# Sheet1.net
KiCad netlist of a schematic drawn in Altium Designer
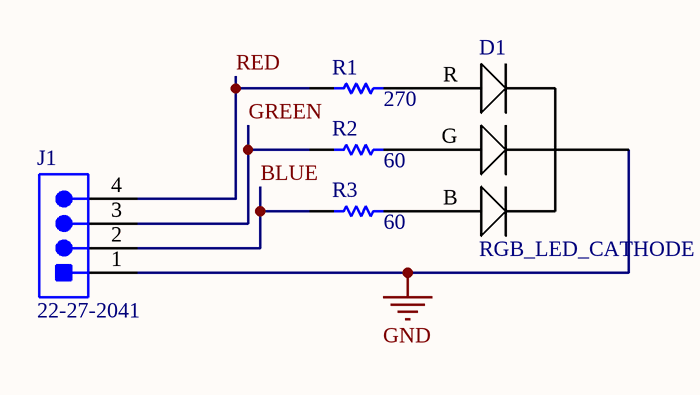
[diagram p0: Sheet1.SchDoc]

(export (version "E")
  (design (tool "Eeschema 10.0.6"))
  (components
    (comp (ref "D1")
      (value "RGB_LED_CATHODE")
      (footprint "RGB_LED_Cathode")
      (libsource (lib "RowanIntegratedLibrary1") (part "RGB_LED_CATHODE"))
    )
    (comp (ref "J1")
      (value "22-27-2041")
      (footprint "MOLX-22-27-2041_V")
      (description "Male Header, Pitch 2.54 mm, 1 x 4 Position, Height 11.7 mm, Tail Length 3.56 mm, RoHS, Bulk")
      (fields (field (name "MANUFACTURER") "Molex"))
      (libsource (lib "Altium Content Vault") (part "CN-1P-M-R4"))
    )
    (comp (ref "R1")
      (value "270")
      (footprint "RESC0805(2012)_L")
      (description "243K 0.125W 1% 0805 (2012 Metric)  SMD")
      (fields (field (name "POWER") "0.125 W") (field (name "TOLERANCE") "1 %"))
      (libsource (lib "Altium Content Vault") (part "RES"))
    )
    (comp (ref "R2")
      (value "60")
      (footprint "RESC0603(1608)_N")
      (description "9M1 0.1W 1% 0603 (1608 Metric)  SMD")
      (fields (field (name "POWER") "0.1 W") (field (name "TOLERANCE") "1 %"))
      (libsource (lib "Altium Content Vault") (part "RES"))
    )
    (comp (ref "R3")
      (value "60")
      (footprint "RESC0603(1608)_N")
      (description "9M1 0.1W 1% 0603 (1608 Metric)  SMD")
      (fields (field (name "POWER") "0.1 W") (field (name "TOLERANCE") "1 %"))
      (libsource (lib "Altium Content Vault") (part "RES"))
    )
  )
  (nets
    (net (code "1") (name "/BLUE") (class "Default")
      (node (ref "J1") (pin "2") (pinfunction "2_2") (pintype "passive"))
      (node (ref "R3") (pin "1") (pinfunction "1_1") (pintype "passive"))
    )
    (net (code "2") (name "/GREEN") (class "Default")
      (node (ref "J1") (pin "3") (pinfunction "3_3") (pintype "passive"))
      (node (ref "R2") (pin "1") (pinfunction "1_1") (pintype "passive"))
    )
    (net (code "3") (name "/RED") (class "Default")
      (node (ref "J1") (pin "4") (pinfunction "4_4") (pintype "passive"))
      (node (ref "R1") (pin "1") (pinfunction "1_1") (pintype "passive"))
    )
    (net (code "4") (name "GND") (class "Default")
      (node (ref "D1") (pin "Common") (pinfunction "9_Common") (pintype "passive"))
      (node (ref "J1") (pin "1") (pinfunction "1_1") (pintype "passive"))
    )
    (net (code "5") (name "Net-(D1-6)") (class "Default")
      (node (ref "D1") (pin "R") (pinfunction "6_R") (pintype "passive"))
      (node (ref "R1") (pin "2") (pinfunction "2_2") (pintype "passive"))
    )
    (net (code "6") (name "Net-(D1-7)") (class "Default")
      (node (ref "D1") (pin "G") (pinfunction "7_G") (pintype "passive"))
      (node (ref "R2") (pin "2") (pinfunction "2_2") (pintype "passive"))
    )
    (net (code "7") (name "Net-(D1-8)") (class "Default")
      (node (ref "D1") (pin "B") (pinfunction "8_B") (pintype "passive"))
      (node (ref "R3") (pin "2") (pinfunction "2_2") (pintype "passive"))
    )
  )
)
